# Irdroid-Rpi.net
KiCad netlist of a schematic drawn in EAGLE
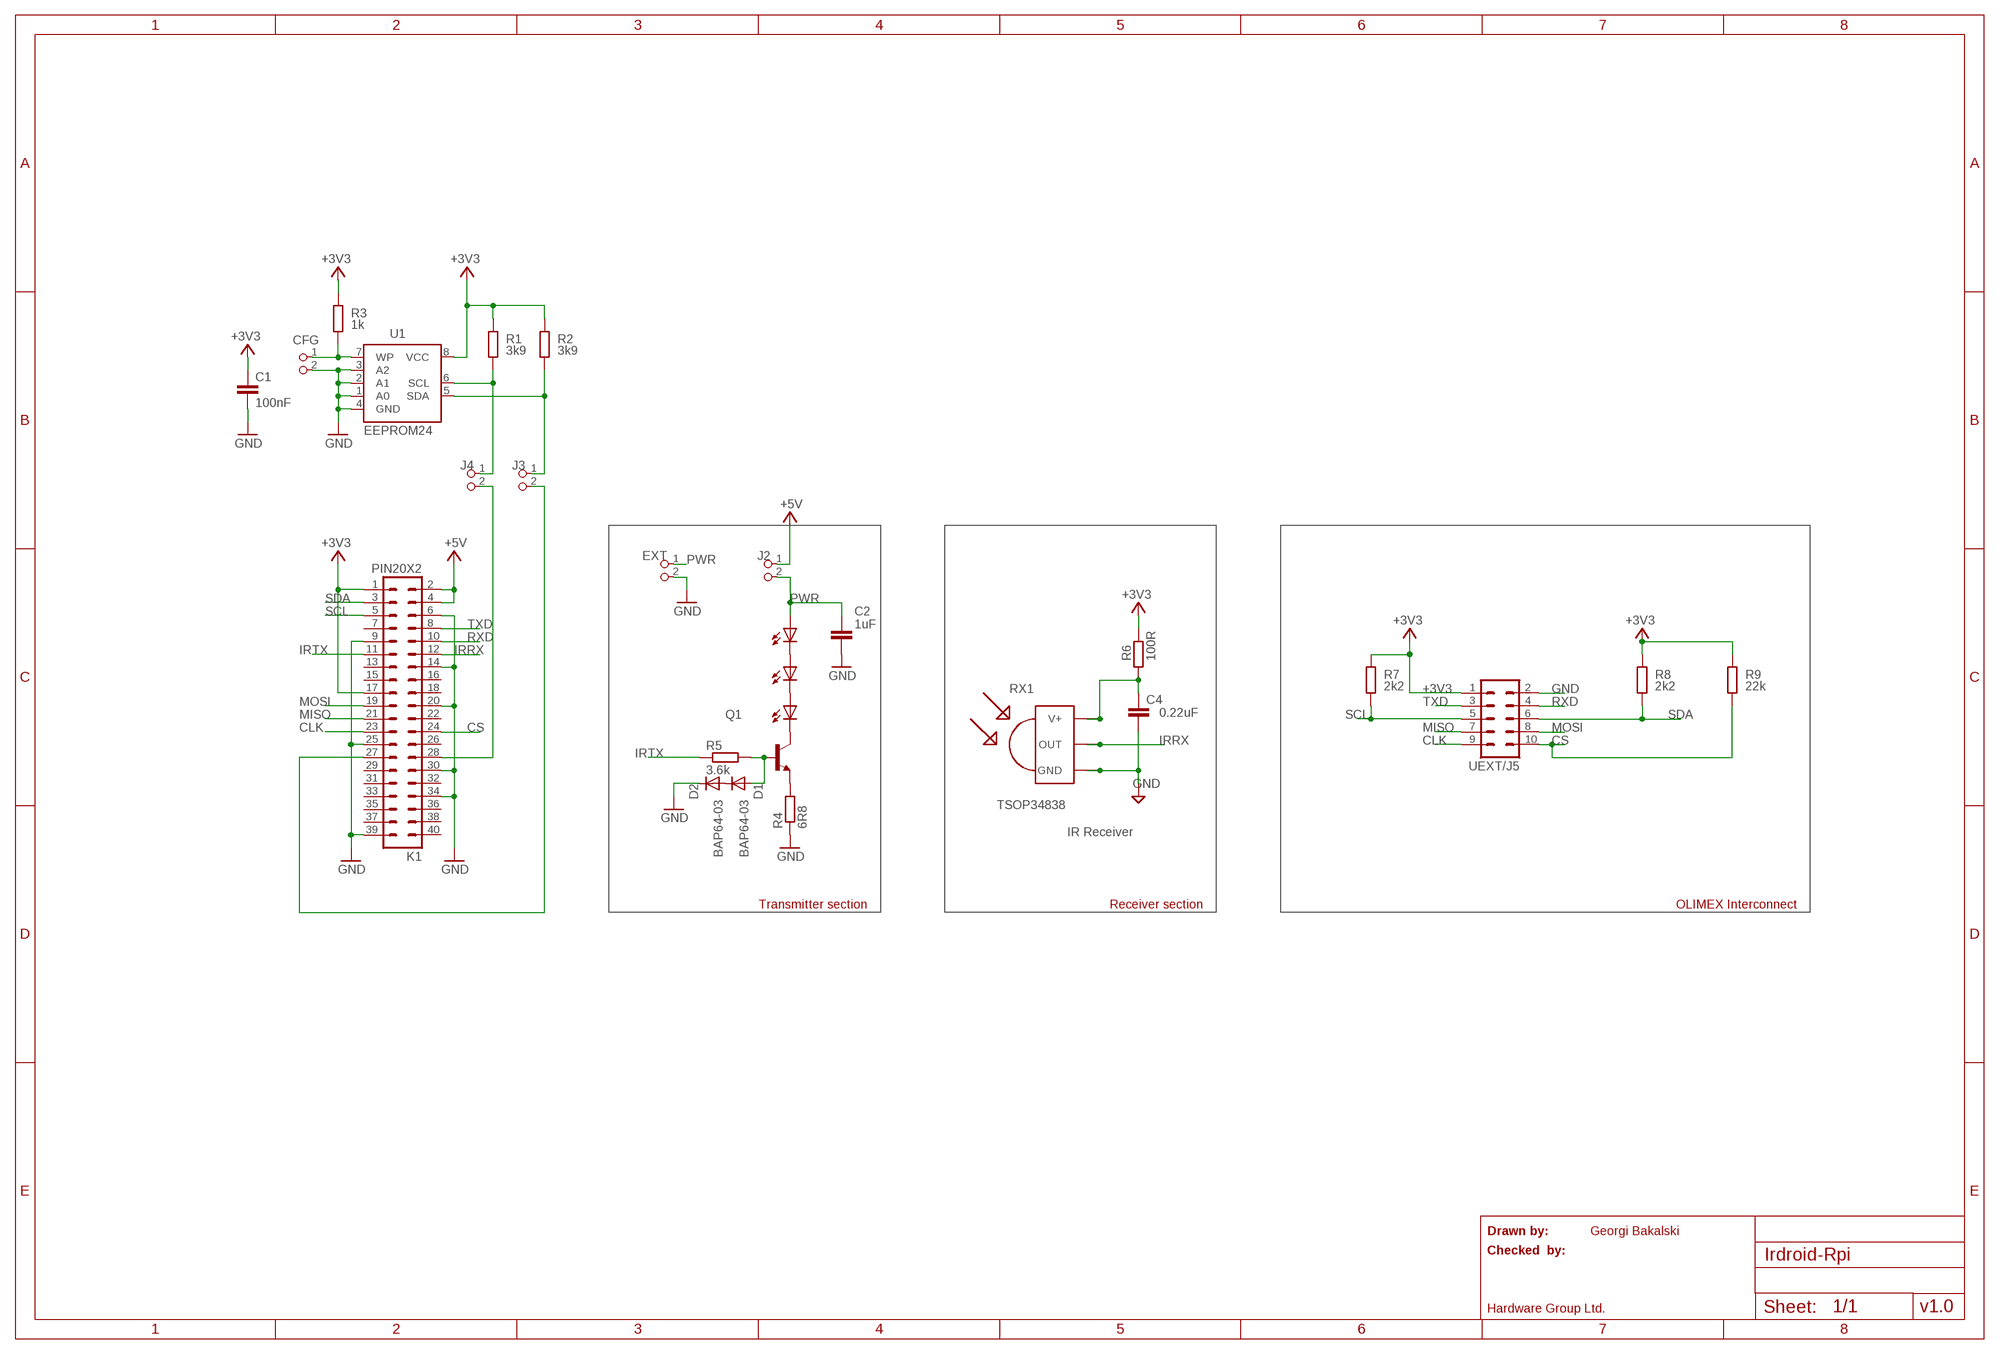
[diagram p0: schematic, sheet 1]

(export (version "E")
  (design (tool "Eeschema 10.0.6"))
  (components
    (comp (ref "C1")
      (value "100nF")
      (footprint "eagle-import:C0805K")
      (libsource (lib "eagle-import") (part "C-EUC0805K"))
    )
    (comp (ref "C2")
      (value "1uF")
      (footprint "eagle-import:C603@1")
      (libsource (lib "eagle-import") (part "CAPACITOR_NPOL-0603"))
    )
    (comp (ref "C4")
      (value "0.22uF")
      (footprint "eagle-import:C603")
      (libsource (lib "eagle-import") (part "CAPC603"))
    )
    (comp (ref "CFG")
      (value "PIN2_100")
      (footprint "eagle-import:PIN_W_2")
      (libsource (lib "eagle-import") (part "PIN2_100"))
    )
    (comp (ref "D1")
      (value "BAP64-03")
      (footprint "eagle-import:DO323")
      (libsource (lib "eagle-import") (part "DIODE-DO323"))
    )
    (comp (ref "D2")
      (value "BAP64-03")
      (footprint "eagle-import:DO323")
      (libsource (lib "eagle-import") (part "DIODE-DO323"))
    )
    (comp (ref "EXT")
      (value "PIN2_100")
      (footprint "eagle-import:PIN_W_2")
      (libsource (lib "eagle-import") (part "PIN2_100"))
    )
    (comp (ref "J2")
      (value "PIN2_100")
      (footprint "eagle-import:PIN_W_2")
      (libsource (lib "eagle-import") (part "PIN2_100"))
    )
    (comp (ref "J3")
      (value "PIN2_100")
      (footprint "eagle-import:PIN_W_2")
      (libsource (lib "eagle-import") (part "PIN2_100"))
    )
    (comp (ref "J4")
      (value "PIN2_100")
      (footprint "eagle-import:PIN_W_2")
      (libsource (lib "eagle-import") (part "PIN2_100"))
    )
    (comp (ref "K1")
      (value "PIN20X2")
      (footprint "eagle-import:PIN_20X2")
      (libsource (lib "eagle-import") (part "PIN20X2"))
    )
    (comp (ref "Q1")
      (value "TRANSISTOR_BJT_NPN-SOT-23-BCE")
      (footprint "eagle-import:SOT-23")
      (libsource (lib "eagle-import") (part "TRANSISTOR_BJT_NPN-SOT-23-BCE"))
    )
    (comp (ref "R1")
      (value "3k9")
      (footprint "eagle-import:M0805")
      (fields (field (name "TOLERANCE") "5%"))
      (libsource (lib "eagle-import") (part "R-EU_M0805"))
    )
    (comp (ref "R2")
      (value "3k9")
      (footprint "eagle-import:M0805")
      (fields (field (name "TOLERANCE") "5%"))
      (libsource (lib "eagle-import") (part "R-EU_M0805"))
    )
    (comp (ref "R3")
      (value "1k")
      (footprint "eagle-import:M0805")
      (fields (field (name "TOLERANCE") "5%"))
      (libsource (lib "eagle-import") (part "R-EU_M0805"))
    )
    (comp (ref "R4")
      (value "6R8")
      (footprint "eagle-import:R1206")
      (libsource (lib "eagle-import") (part "R-EU_R1206"))
    )
    (comp (ref "R5")
      (value "3.6k")
      (footprint "eagle-import:R0603")
      (libsource (lib "eagle-import") (part "R-EU_R0603"))
    )
    (comp (ref "R6")
      (value "100R")
      (footprint "eagle-import:R603")
      (libsource (lib "eagle-import") (part "RESISTORR603"))
    )
    (comp (ref "R7")
      (value "2k2")
      (footprint "eagle-import:M0805")
      (fields (field (name "TOLERANCE") "5%"))
      (libsource (lib "eagle-import") (part "R-EU_M0805"))
    )
    (comp (ref "R8")
      (value "2k2")
      (footprint "eagle-import:M0805")
      (fields (field (name "TOLERANCE") "5%"))
      (libsource (lib "eagle-import") (part "R-EU_M0805"))
    )
    (comp (ref "R9")
      (value "22k")
      (footprint "eagle-import:M0805")
      (fields (field (name "TOLERANCE") "5%"))
      (libsource (lib "eagle-import") (part "R-EU_M0805"))
    )
    (comp (ref "RX1")
      (value "TSOP34838")
      (footprint "eagle-import:TSOP18XX")
      (libsource (lib "eagle-import") (part "TSOP4838"))
    )
    (comp (ref "U$5")
      (value "IRLED5MM")
      (footprint "eagle-import:IRLED_HOLDER")
      (libsource (lib "eagle-import") (part "IRLED5MM"))
    )
    (comp (ref "U$6")
      (value "IRLED5MM")
      (footprint "eagle-import:IRLED_HOLDER")
      (libsource (lib "eagle-import") (part "IRLED5MM"))
    )
    (comp (ref "U$7")
      (value "IRLED5MM")
      (footprint "eagle-import:IRLED_HOLDER")
      (libsource (lib "eagle-import") (part "IRLED5MM"))
    )
    (comp (ref "U1")
      (value "EEPROM24")
      (footprint "eagle-import:SOIC8")
      (libsource (lib "eagle-import") (part "EEPROM24"))
    )
    (comp (ref "UEXT/J5")
      (value "ML10")
      (footprint "eagle-import:ML10")
      (libsource (lib "eagle-import") (part "ML10"))
    )
  )
  (nets
    (net (code "1") (name "+3V3") (class "Default")
      (node (ref "C1") (pin "1") (pinfunction "1_1") (pintype "passive"))
      (node (ref "K1") (pin "1") (pinfunction "1_1") (pintype "passive"))
      (node (ref "K1") (pin "17") (pinfunction "17_17") (pintype "passive"))
      (node (ref "R1") (pin "2") (pinfunction "2_2") (pintype "passive"))
      (node (ref "R2") (pin "2") (pinfunction "2_2") (pintype "passive"))
      (node (ref "R3") (pin "2") (pinfunction "2_2") (pintype "passive"))
      (node (ref "R6") (pin "2") (pinfunction "2_2") (pintype "passive"))
      (node (ref "R7") (pin "2") (pinfunction "2_2") (pintype "passive"))
      (node (ref "R8") (pin "2") (pinfunction "2_2") (pintype "passive"))
      (node (ref "R9") (pin "2") (pinfunction "2_2") (pintype "passive"))
      (node (ref "U1") (pin "8") (pinfunction "VCC_8") (pintype "power_in"))
      (node (ref "UEXT/J5") (pin "1") (pinfunction "1_1") (pintype "passive"))
    )
    (net (code "2") (name "+5V") (class "Default")
      (node (ref "J2") (pin "1") (pinfunction "1_1") (pintype "passive"))
      (node (ref "K1") (pin "2") (pinfunction "2_2") (pintype "passive"))
      (node (ref "K1") (pin "4") (pinfunction "4_4") (pintype "passive"))
    )
    (net (code "3") (name "/CLK") (class "Default")
      (node (ref "K1") (pin "23") (pinfunction "23_23") (pintype "passive"))
      (node (ref "UEXT/J5") (pin "9") (pinfunction "9_9") (pintype "passive"))
    )
    (net (code "4") (name "/CS") (class "Default")
      (node (ref "K1") (pin "24") (pinfunction "24_24") (pintype "passive"))
      (node (ref "R9") (pin "1") (pinfunction "1_1") (pintype "passive"))
      (node (ref "UEXT/J5") (pin "10") (pinfunction "10_10") (pintype "passive"))
    )
    (net (code "5") (name "/IRRX") (class "Default")
      (node (ref "K1") (pin "12") (pinfunction "12_12") (pintype "passive"))
      (node (ref "RX1") (pin "OUT") (pinfunction "OUT_OUT") (pintype "bidirectional"))
    )
    (net (code "6") (name "/IRTX") (class "Default")
      (node (ref "K1") (pin "11") (pinfunction "11_11") (pintype "passive"))
      (node (ref "R5") (pin "1") (pinfunction "1_1") (pintype "passive"))
    )
    (net (code "7") (name "/MISO") (class "Default")
      (node (ref "K1") (pin "21") (pinfunction "21_21") (pintype "passive"))
      (node (ref "UEXT/J5") (pin "7") (pinfunction "7_7") (pintype "passive"))
    )
    (net (code "8") (name "/MOSI") (class "Default")
      (node (ref "K1") (pin "19") (pinfunction "19_19") (pintype "passive"))
      (node (ref "UEXT/J5") (pin "8") (pinfunction "8_8") (pintype "passive"))
    )
    (net (code "9") (name "/PWR") (class "Default")
      (node (ref "C2") (pin "1") (pinfunction "1_1") (pintype "passive"))
      (node (ref "EXT") (pin "1") (pinfunction "1_1") (pintype "passive"))
      (node (ref "J2") (pin "2") (pinfunction "2_2") (pintype "passive"))
      (node (ref "U$7") (pin "A") (pinfunction "A_A") (pintype "passive"))
    )
    (net (code "10") (name "/RXD") (class "Default")
      (node (ref "K1") (pin "10") (pinfunction "10_10") (pintype "passive"))
      (node (ref "UEXT/J5") (pin "4") (pinfunction "4_4") (pintype "passive"))
    )
    (net (code "11") (name "/SCL") (class "Default")
      (node (ref "K1") (pin "5") (pinfunction "5_5") (pintype "passive"))
      (node (ref "R7") (pin "1") (pinfunction "1_1") (pintype "passive"))
      (node (ref "UEXT/J5") (pin "5") (pinfunction "5_5") (pintype "passive"))
    )
    (net (code "12") (name "/SDA") (class "Default")
      (node (ref "K1") (pin "3") (pinfunction "3_3") (pintype "passive"))
      (node (ref "R8") (pin "1") (pinfunction "1_1") (pintype "passive"))
      (node (ref "UEXT/J5") (pin "6") (pinfunction "6_6") (pintype "passive"))
    )
    (net (code "13") (name "/TXD") (class "Default")
      (node (ref "K1") (pin "8") (pinfunction "8_8") (pintype "passive"))
      (node (ref "UEXT/J5") (pin "3") (pinfunction "3_3") (pintype "passive"))
    )
    (net (code "14") (name "GND") (class "Default")
      (node (ref "C1") (pin "2") (pinfunction "2_2") (pintype "passive"))
      (node (ref "C2") (pin "2") (pinfunction "2_2") (pintype "passive"))
      (node (ref "C4") (pin "2") (pinfunction "2_2") (pintype "passive"))
      (node (ref "CFG") (pin "2") (pinfunction "2_2") (pintype "passive"))
      (node (ref "D2") (pin "C") (pinfunction "C_C") (pintype "passive"))
      (node (ref "EXT") (pin "2") (pinfunction "2_2") (pintype "passive"))
      (node (ref "K1") (pin "14") (pinfunction "14_14") (pintype "passive"))
      (node (ref "K1") (pin "20") (pinfunction "20_20") (pintype "passive"))
      (node (ref "K1") (pin "25") (pinfunction "25_25") (pintype "passive"))
      (node (ref "K1") (pin "30") (pinfunction "30_30") (pintype "passive"))
      (node (ref "K1") (pin "34") (pinfunction "34_34") (pintype "passive"))
      (node (ref "K1") (pin "39") (pinfunction "39_39") (pintype "passive"))
      (node (ref "K1") (pin "6") (pinfunction "6_6") (pintype "passive"))
      (node (ref "K1") (pin "9") (pinfunction "9_9") (pintype "passive"))
      (node (ref "R4") (pin "1") (pinfunction "1_1") (pintype "passive"))
      (node (ref "RX1") (pin "GND") (pinfunction "GND_GND") (pintype "bidirectional"))
      (node (ref "U1") (pin "1") (pinfunction "A0_1") (pintype "input"))
      (node (ref "U1") (pin "2") (pinfunction "A1_2") (pintype "input"))
      (node (ref "U1") (pin "3") (pinfunction "A2_3") (pintype "input"))
      (node (ref "U1") (pin "4") (pinfunction "GND_4") (pintype "power_in"))
      (node (ref "UEXT/J5") (pin "2") (pinfunction "2_2") (pintype "passive"))
    )
    (net (code "15") (name "Net-(D1-PadC)") (class "Default")
      (node (ref "D1") (pin "C") (pinfunction "C_C") (pintype "passive"))
      (node (ref "D2") (pin "A") (pinfunction "A_A") (pintype "passive"))
    )
    (net (code "16") (name "Net-(J3-Pad2)") (class "Default")
      (node (ref "J3") (pin "2") (pinfunction "2_2") (pintype "passive"))
      (node (ref "K1") (pin "27") (pinfunction "27_27") (pintype "passive"))
    )
    (net (code "17") (name "Net-(J4-Pad2)") (class "Default")
      (node (ref "J4") (pin "2") (pinfunction "2_2") (pintype "passive"))
      (node (ref "K1") (pin "28") (pinfunction "28_28") (pintype "passive"))
    )
    (net (code "18") (name "Net-(Q1-B)") (class "Default")
      (node (ref "D1") (pin "A") (pinfunction "A_A") (pintype "passive"))
      (node (ref "Q1") (pin "1") (pinfunction "B_1") (pintype "passive"))
      (node (ref "R5") (pin "2") (pinfunction "2_2") (pintype "passive"))
    )
    (net (code "19") (name "Net-(Q1-C)") (class "Default")
      (node (ref "Q1") (pin "2") (pinfunction "C_2") (pintype "passive"))
      (node (ref "U$5") (pin "K") (pinfunction "C_K") (pintype "passive"))
    )
    (net (code "20") (name "Net-(Q1-E)") (class "Default")
      (node (ref "Q1") (pin "3") (pinfunction "E_3") (pintype "passive"))
      (node (ref "R4") (pin "2") (pinfunction "2_2") (pintype "passive"))
    )
    (net (code "21") (name "Net-(RX1-V+)") (class "Default")
      (node (ref "C4") (pin "1") (pinfunction "1_1") (pintype "passive"))
      (node (ref "R6") (pin "1") (pinfunction "1_1") (pintype "passive"))
      (node (ref "RX1") (pin "VCC") (pinfunction "V+_VCC") (pintype "bidirectional"))
    )
    (net (code "22") (name "Net-(U$6-C)") (class "Default")
      (node (ref "U$5") (pin "A") (pinfunction "A_A") (pintype "passive"))
      (node (ref "U$6") (pin "K") (pinfunction "C_K") (pintype "passive"))
    )
    (net (code "23") (name "Net-(U$7-C)") (class "Default")
      (node (ref "U$6") (pin "A") (pinfunction "A_A") (pintype "passive"))
      (node (ref "U$7") (pin "K") (pinfunction "C_K") (pintype "passive"))
    )
    (net (code "24") (name "Net-(U1-SCL)") (class "Default")
      (node (ref "J4") (pin "1") (pinfunction "1_1") (pintype "passive"))
      (node (ref "R1") (pin "1") (pinfunction "1_1") (pintype "passive"))
      (node (ref "U1") (pin "6") (pinfunction "SCL_6") (pintype "input"))
    )
    (net (code "25") (name "Net-(U1-SDA)") (class "Default")
      (node (ref "J3") (pin "1") (pinfunction "1_1") (pintype "passive"))
      (node (ref "R2") (pin "1") (pinfunction "1_1") (pintype "passive"))
      (node (ref "U1") (pin "5") (pinfunction "SDA_5") (pintype "bidirectional"))
    )
    (net (code "26") (name "Net-(U1-WP)") (class "Default")
      (node (ref "CFG") (pin "1") (pinfunction "1_1") (pintype "passive"))
      (node (ref "R3") (pin "1") (pinfunction "1_1") (pintype "passive"))
      (node (ref "U1") (pin "7") (pinfunction "WP_7") (pintype "input"))
    )
    (net (code "27") (name "unconnected-(K1-Pad7)") (class "Default")
      (node (ref "K1") (pin "7") (pinfunction "7_7") (pintype "passive"))
    )
    (net (code "28") (name "unconnected-(K1-Pad13)") (class "Default")
      (node (ref "K1") (pin "13") (pinfunction "13_13") (pintype "passive"))
    )
    (net (code "29") (name "unconnected-(K1-Pad15)") (class "Default")
      (node (ref "K1") (pin "15") (pinfunction "15_15") (pintype "passive"))
    )
    (net (code "30") (name "unconnected-(K1-Pad16)") (class "Default")
      (node (ref "K1") (pin "16") (pinfunction "16_16") (pintype "passive"))
    )
    (net (code "31") (name "unconnected-(K1-Pad18)") (class "Default")
      (node (ref "K1") (pin "18") (pinfunction "18_18") (pintype "passive"))
    )
    (net (code "32") (name "unconnected-(K1-Pad22)") (class "Default")
      (node (ref "K1") (pin "22") (pinfunction "22_22") (pintype "passive"))
    )
    (net (code "33") (name "unconnected-(K1-Pad26)") (class "Default")
      (node (ref "K1") (pin "26") (pinfunction "26_26") (pintype "passive"))
    )
    (net (code "34") (name "unconnected-(K1-Pad29)") (class "Default")
      (node (ref "K1") (pin "29") (pinfunction "29_29") (pintype "passive"))
    )
    (net (code "35") (name "unconnected-(K1-Pad31)") (class "Default")
      (node (ref "K1") (pin "31") (pinfunction "31_31") (pintype "passive"))
    )
    (net (code "36") (name "unconnected-(K1-Pad32)") (class "Default")
      (node (ref "K1") (pin "32") (pinfunction "32_32") (pintype "passive"))
    )
    (net (code "37") (name "unconnected-(K1-Pad33)") (class "Default")
      (node (ref "K1") (pin "33") (pinfunction "33_33") (pintype "passive"))
    )
    (net (code "38") (name "unconnected-(K1-Pad35)") (class "Default")
      (node (ref "K1") (pin "35") (pinfunction "35_35") (pintype "passive"))
    )
    (net (code "39") (name "unconnected-(K1-Pad36)") (class "Default")
      (node (ref "K1") (pin "36") (pinfunction "36_36") (pintype "passive"))
    )
    (net (code "40") (name "unconnected-(K1-Pad37)") (class "Default")
      (node (ref "K1") (pin "37") (pinfunction "37_37") (pintype "passive"))
    )
    (net (code "41") (name "unconnected-(K1-Pad38)") (class "Default")
      (node (ref "K1") (pin "38") (pinfunction "38_38") (pintype "passive"))
    )
    (net (code "42") (name "unconnected-(K1-Pad40)") (class "Default")
      (node (ref "K1") (pin "40") (pinfunction "40_40") (pintype "passive"))
    )
  )
)
